# DVR10983PWPR.net
KiCad netlist of a schematic drawn in Altium Designer
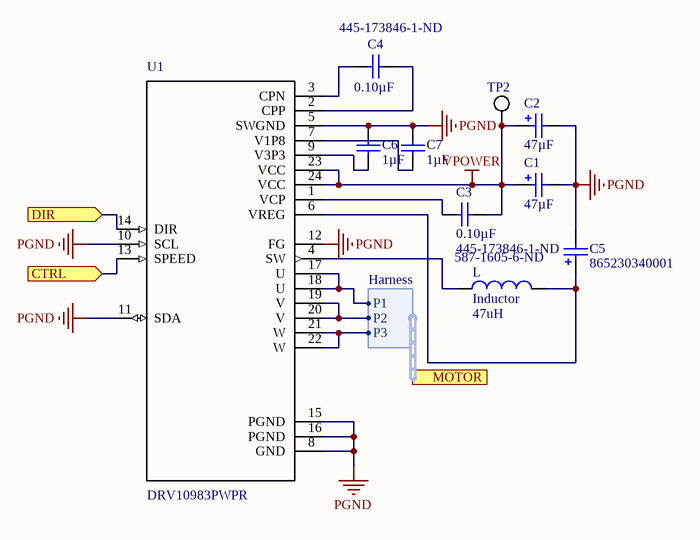
[diagram p0: DVR10983PWPR.SchDoc]

(export (version "E")
  (design (tool "Eeschema 10.0.6"))
  (components
    (comp (ref "C1")
      (value "865080645012")
      (footprint "CAP 6.6x6.6mm")
      (description "CAP 47 UF 20% 50 V")
      (fields
        (field (name "MANUFACTURER") "Wurth Electronics Inc")
        (field (name "TOLERANCE") "±20%")
        (field (name "CAPACITANCE") "47µF")
      )
      (libsource (lib "ResCap") (part "865080645012"))
    )
    (comp (ref "C2")
      (value "865080645012")
      (footprint "CAP 6.6x6.6mm")
      (description "CAP 47 UF 20% 50 V")
      (fields
        (field (name "MANUFACTURER") "Wurth Electronics Inc")
        (field (name "TOLERANCE") "±20%")
        (field (name "CAPACITANCE") "47µF")
      )
      (libsource (lib "ResCap") (part "865080645012"))
    )
    (comp (ref "C3")
      (value "CL10B104KB8SFNC")
      (footprint "0603")
      (description "CAP CER 0.1UF 50V X7R 0603")
      (fields
        (field (name "MANUFACTURER") "Samsung Electro-Mechanics America, Inc.")
        (field (name "TOLERANCE") "±10%")
        (field (name "CAPACITANCE") "0.10µF")
        (field (name "SUPPLIER PART NUMBER 1") "445-173846-1-ND")
      )
      (libsource (lib "ResCap") (part "CL10B104KB8SFNC"))
    )
    (comp (ref "C4")
      (value "CL10B104KB8SFNC")
      (footprint "0603")
      (description "CAP CER 0.1UF 50V X7R 0603")
      (fields
        (field (name "MANUFACTURER") "Samsung Electro-Mechanics America, Inc.")
        (field (name "TOLERANCE") "±10%")
        (field (name "CAPACITANCE") "0.10µF")
        (field (name "SUPPLIER PART NUMBER 1") "445-173846-1-ND")
      )
      (libsource (lib "ResCap") (part "CL10B104KB8SFNC"))
    )
    (comp (ref "C5")
      (value "865230340001")
      (footprint "CAP 4.3x4.3mm")
      (description "CAP 10 UF 20% 16 V")
      (fields (field (name "MANUFACTURER") "Wurth Electronics Inc") (field (name "TOLERANCE") "±20%"))
      (libsource (lib "ResCap") (part "865230340001"))
    )
    (comp (ref "C6")
      (value "CL21B105KBFNFNE")
      (footprint "0805")
      (description "CAP CER 1UF 50V X7R 0805")
      (fields
        (field (name "MANUFACTURER") "Samsung Electro-Mechanics America, Inc.")
        (field (name "TOLERANCE") "±10%")
        (field (name "CAPACITANCE") "1µF")
      )
      (libsource (lib "ResCap") (part "CL21B105KBFNFNE"))
    )
    (comp (ref "C7")
      (value "CL21B105KBFNFNE")
      (footprint "0805")
      (description "CAP CER 1UF 50V X7R 0805")
      (fields
        (field (name "MANUFACTURER") "Samsung Electro-Mechanics America, Inc.")
        (field (name "TOLERANCE") "±10%")
        (field (name "CAPACITANCE") "1µF")
      )
      (libsource (lib "ResCap") (part "CL21B105KBFNFNE"))
    )
    (comp (ref "L")
      (value "Inductor")
      (footprint "*INDC2012X100N")
      (description "CBC2012T470M")
      (fields
        (field (name "ALTIUM_VALUE") "47uH")
        (field (name "SUPPLIER PART NUMBER 1") "587-1605-6-ND")
        (field (name "PUBLISHER") "Altium Limited")
      )
      (libsource (lib "Miscellaneous Devices") (part "Inductor"))
    )
    (comp (ref "TP2")
      (value "testpoint")
      (footprint "0805 testpoint")
      (description "Testpoint")
      (libsource (lib "BrushlessDrive") (part "testpoint"))
    )
    (comp (ref "U1")
      (value "DRV10983PWPR")
      (footprint "*SOP65P640X120-25N")
      (libsource (lib "DRV10983PWPR") (part "DRV10983PWPR"))
    )
  )
  (nets
    (net (code "2") (name "/CTRL") (class "Default")
      (node (ref "U1") (pin "13") (pinfunction "SPEED_13") (pintype "input"))
    )
    (net (code "3") (name "/DIR") (class "Default")
      (node (ref "U1") (pin "14") (pinfunction "DIR_14") (pintype "input"))
    )
    (net (code "5") (name "Net-(U1-CPN)") (class "Default")
      (node (ref "C4") (pin "1") (pinfunction "1_1") (pintype "passive"))
      (node (ref "U1") (pin "3") (pinfunction "CPN_3") (pintype "power_in"))
    )
    (net (code "6") (name "Net-(U1-CPP)") (class "Default")
      (node (ref "C4") (pin "2") (pinfunction "2_2") (pintype "passive"))
      (node (ref "U1") (pin "2") (pinfunction "CPP_2") (pintype "power_in"))
    )
    (net (code "7") (name "Net-(U1-SW)") (class "Default")
      (node (ref "L") (pin "1") (pinfunction "1_1") (pintype "passive"))
      (node (ref "U1") (pin "4") (pinfunction "SW_4") (pintype "output"))
    )
    (net (code "8") (name "Net-(U1-U-Pad17)") (class "Default")
      (node (ref "U1") (pin "17") (pinfunction "U_17") (pintype "passive"))
      (node (ref "U1") (pin "18") (pinfunction "U_18") (pintype "passive"))
    )
    (net (code "9") (name "Net-(U1-V-Pad19)") (class "Default")
      (node (ref "U1") (pin "19") (pinfunction "V_19") (pintype "passive"))
      (node (ref "U1") (pin "20") (pinfunction "V_20") (pintype "passive"))
    )
    (net (code "10") (name "Net-(U1-V1P8)") (class "Default")
      (node (ref "C7") (pin "1") (pinfunction "1_1") (pintype "passive"))
      (node (ref "U1") (pin "7") (pinfunction "V1P8_7") (pintype "power_in"))
    )
    (net (code "11") (name "Net-(U1-V3P3)") (class "Default")
      (node (ref "C6") (pin "1") (pinfunction "1_1") (pintype "passive"))
      (node (ref "U1") (pin "9") (pinfunction "V3P3_9") (pintype "power_in"))
    )
    (net (code "12") (name "Net-(U1-VCP)") (class "Default")
      (node (ref "C3") (pin "1") (pinfunction "1_1") (pintype "passive"))
      (node (ref "U1") (pin "1") (pinfunction "VCP_1") (pintype "power_in"))
    )
    (net (code "13") (name "Net-(U1-VREG)") (class "Default")
      (node (ref "C5") (pin "1") (pinfunction "1_1") (pintype "passive"))
      (node (ref "L") (pin "2") (pinfunction "2_2") (pintype "passive"))
      (node (ref "U1") (pin "6") (pinfunction "VREG_6") (pintype "power_in"))
    )
    (net (code "14") (name "Net-(U1-W-Pad21)") (class "Default")
      (node (ref "U1") (pin "21") (pinfunction "W_21") (pintype "passive"))
      (node (ref "U1") (pin "22") (pinfunction "W_22") (pintype "passive"))
    )
    (net (code "15") (name "PGND") (class "Default")
      (node (ref "C1") (pin "2") (pinfunction "2_2") (pintype "passive"))
      (node (ref "C2") (pin "2") (pinfunction "2_2") (pintype "passive"))
      (node (ref "C5") (pin "2") (pinfunction "2_2") (pintype "passive"))
      (node (ref "C6") (pin "2") (pinfunction "2_2") (pintype "passive"))
      (node (ref "C7") (pin "2") (pinfunction "2_2") (pintype "passive"))
      (node (ref "U1") (pin "10") (pinfunction "SCL_10") (pintype "input"))
      (node (ref "U1") (pin "11") (pinfunction "SDA_11") (pintype "bidirectional"))
      (node (ref "U1") (pin "12") (pinfunction "FG_12") (pintype "passive"))
      (node (ref "U1") (pin "15") (pinfunction "PGND_15") (pintype "power_in"))
      (node (ref "U1") (pin "16") (pinfunction "PGND_16") (pintype "power_in"))
      (node (ref "U1") (pin "5") (pinfunction "SWGND_5") (pintype "power_in"))
      (node (ref "U1") (pin "8") (pinfunction "GND_8") (pintype "power_in"))
    )
    (net (code "16") (name "VPOWER") (class "Default")
      (node (ref "C1") (pin "1") (pinfunction "1_1") (pintype "passive"))
      (node (ref "C2") (pin "1") (pinfunction "1_1") (pintype "passive"))
      (node (ref "C3") (pin "2") (pinfunction "2_2") (pintype "passive"))
      (node (ref "TP2") (pin "1") (pinfunction "1_1") (pintype "passive"))
      (node (ref "U1") (pin "23") (pinfunction "VCC_23") (pintype "power_in"))
      (node (ref "U1") (pin "24") (pinfunction "VCC_24") (pintype "power_in"))
    )
  )
)
